# 1V8_SUPPLY.net
KiCad netlist of a schematic drawn in Altium Designer
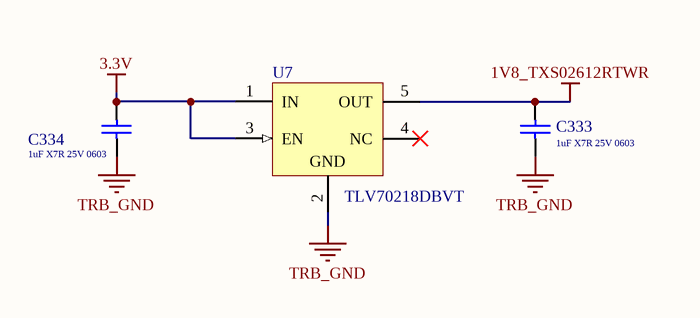
[diagram p0: 1V8_SUPPLY.SchDoc]

(export (version "E")
  (design (tool "Eeschema 10.0.6"))
  (components
    (comp (ref "C333")
      (value "Cap_Murata_GCJ188R71E105KA01J_1uF")
      (footprint "Cap_Murata_GCJ188R71E105KA01J_1uF")
      (description "CAP CER 1uF 25V X7R 0603")
      (fields (field (name "CAPACITANCE") "1uF X7R 25V 0603"))
      (libsource (lib "Cap_Murata_GCJ188R71E105KA01J_1uF") (part "Cap_Murata_GCJ188R71E105KA01J_1uF"))
    )
    (comp (ref "C334")
      (value "Cap_Murata_GCJ188R71E105KA01J_1uF")
      (footprint "Cap_Murata_GCJ188R71E105KA01J_1uF")
      (description "CAP CER 1uF 25V X7R 0603")
      (fields (field (name "CAPACITANCE") "1uF X7R 25V 0603"))
      (libsource (lib "Cap_Murata_GCJ188R71E105KA01J_1uF") (part "Cap_Murata_GCJ188R71E105KA01J_1uF"))
    )
    (comp (ref "U7")
      (value "TLV70218DBVT")
      (footprint "TI-DBV5_N")
      (fields (field (name "MANUFACTURER") "Texas Instruments"))
      (libsource (lib "IC_Texas_Instruments_TLV70218DBVT") (part "TLV70218DBVT"))
    )
  )
  (nets
    (net (code "1") (name "1V8_TXS02612RTWR") (class "Default")
      (node (ref "C333") (pin "2") (pinfunction "2_2") (pintype "passive"))
      (node (ref "U7") (pin "5") (pinfunction "OUT_5") (pintype "power_in"))
    )
    (net (code "2") (name "3.3V") (class "Default")
      (node (ref "C334") (pin "2") (pinfunction "2_2") (pintype "passive"))
      (node (ref "U7") (pin "1") (pinfunction "IN_1") (pintype "power_in"))
      (node (ref "U7") (pin "3") (pinfunction "EN_3") (pintype "input"))
    )
    (net (code "3") (name "TRB_GND") (class "Default")
      (node (ref "C333") (pin "1") (pinfunction "1_1") (pintype "passive"))
      (node (ref "C334") (pin "1") (pinfunction "1_1") (pintype "passive"))
      (node (ref "U7") (pin "2") (pinfunction "GND_2") (pintype "power_in"))
    )
    (net (code "4") (name "unconnected-(U7-NC-Pad4)") (class "Default")
      (node (ref "U7") (pin "4") (pinfunction "NC_4") (pintype "passive+no_connect"))
    )
  )
)
